# SingleBoard.net
KiCad netlist of a schematic drawn in EAGLE
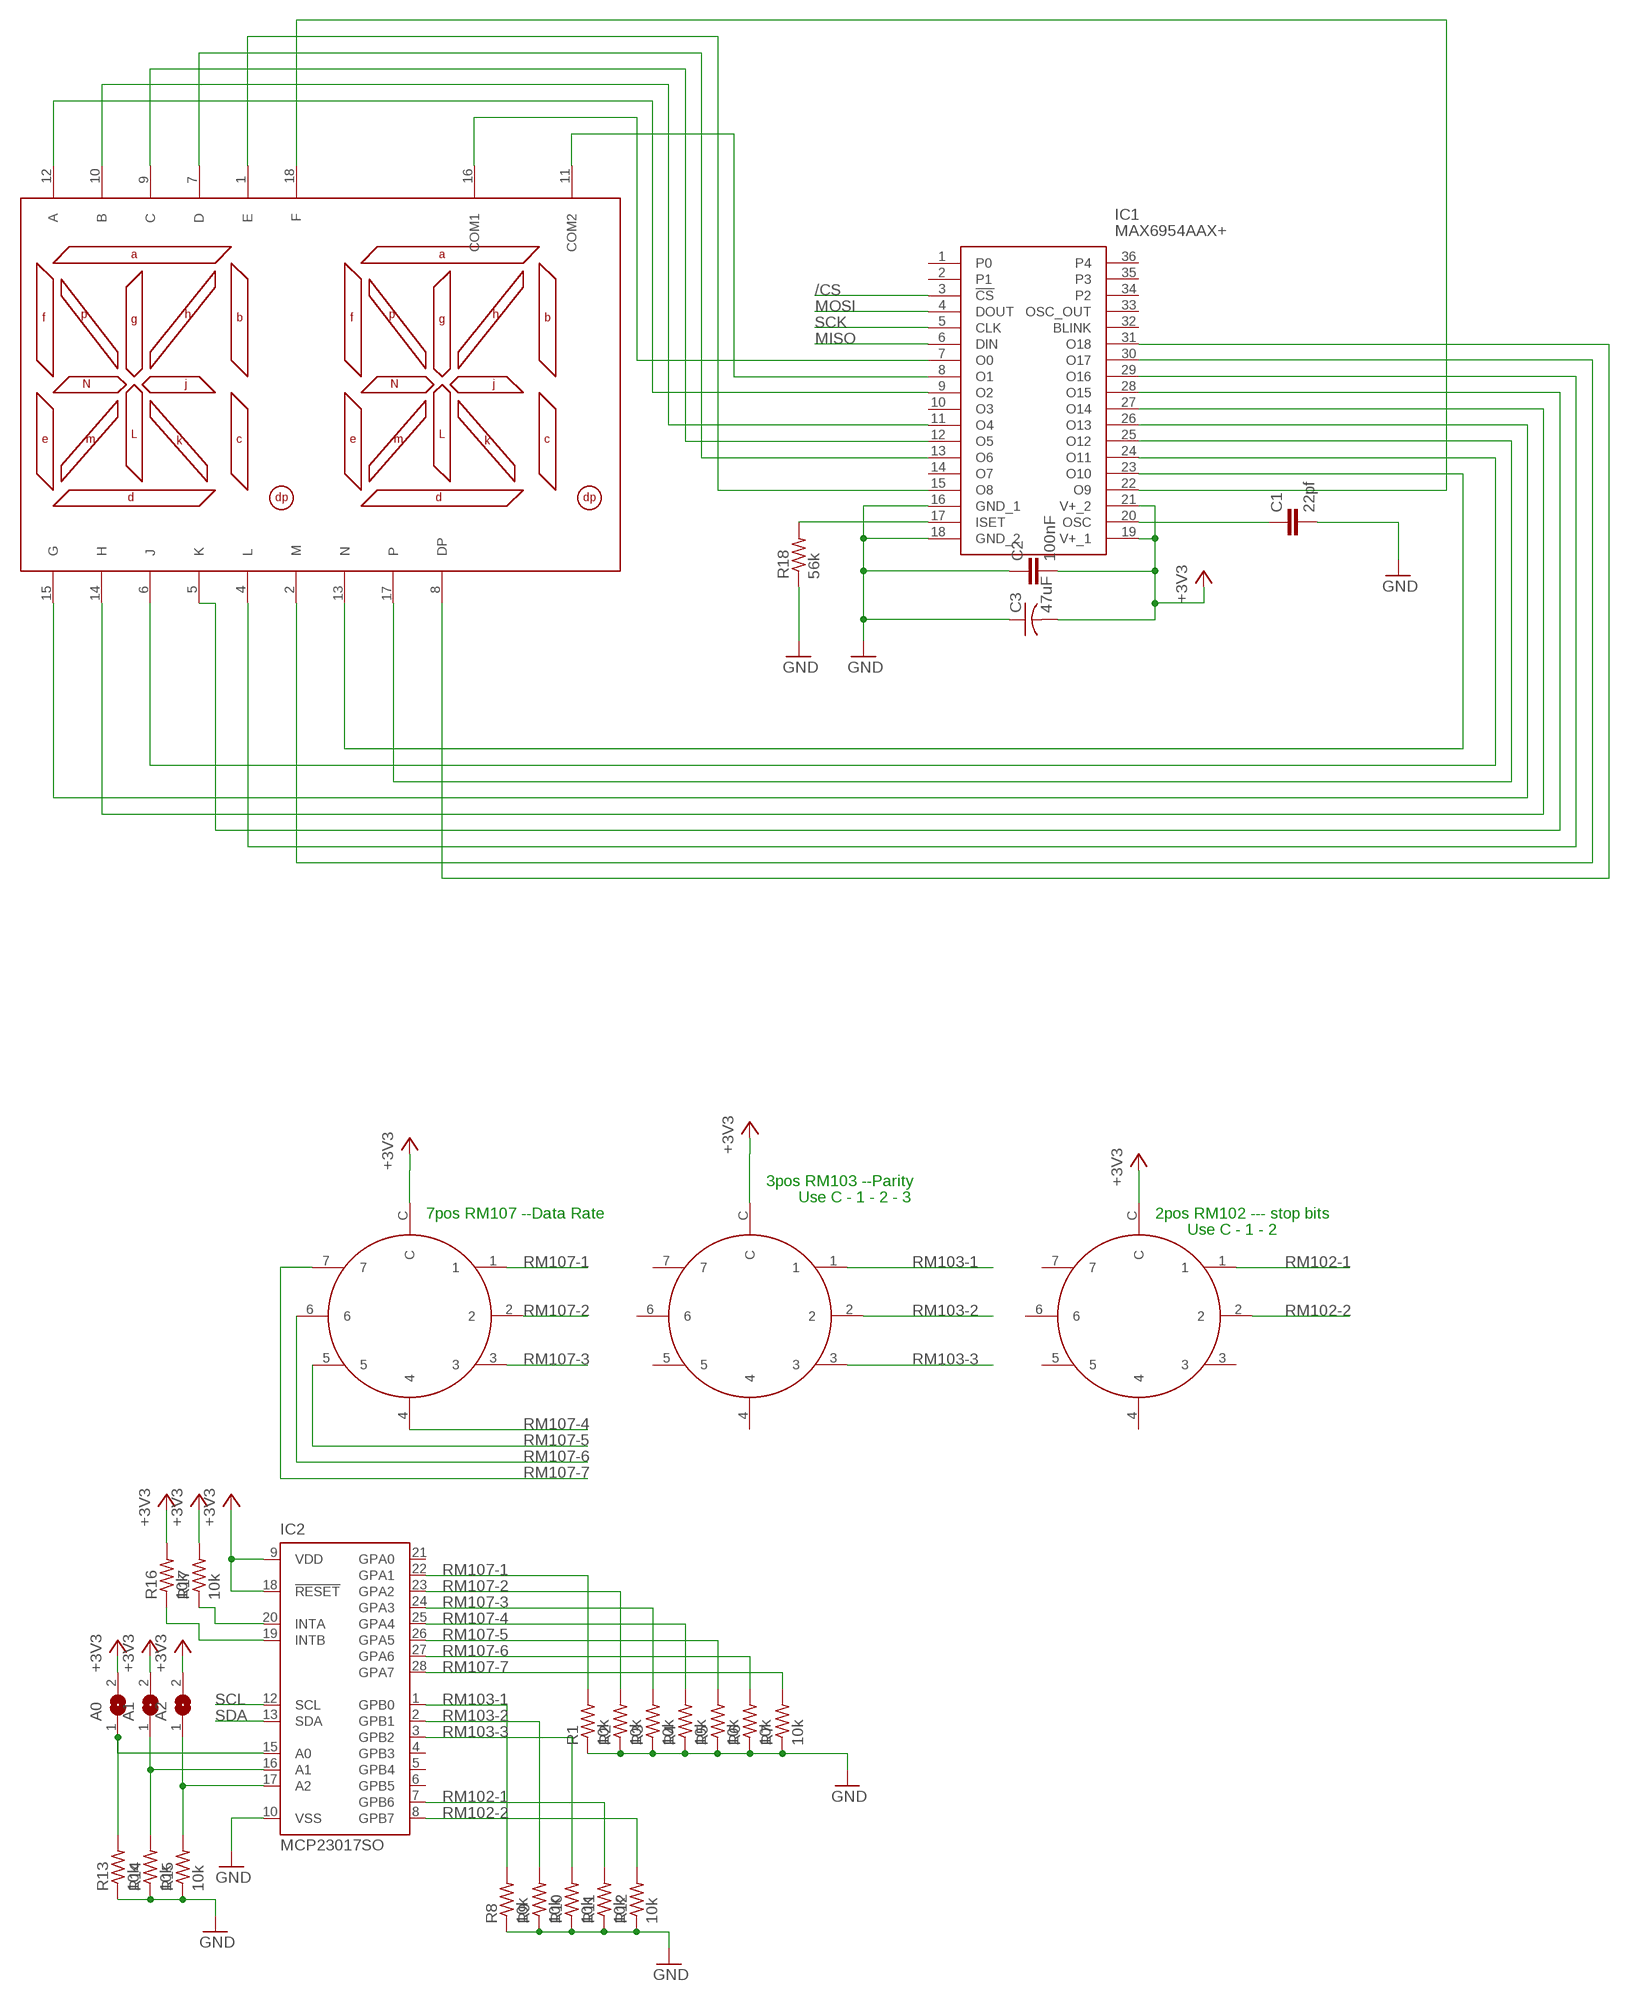
[diagram p0: schematic, sheet 1, part 1 of 2]
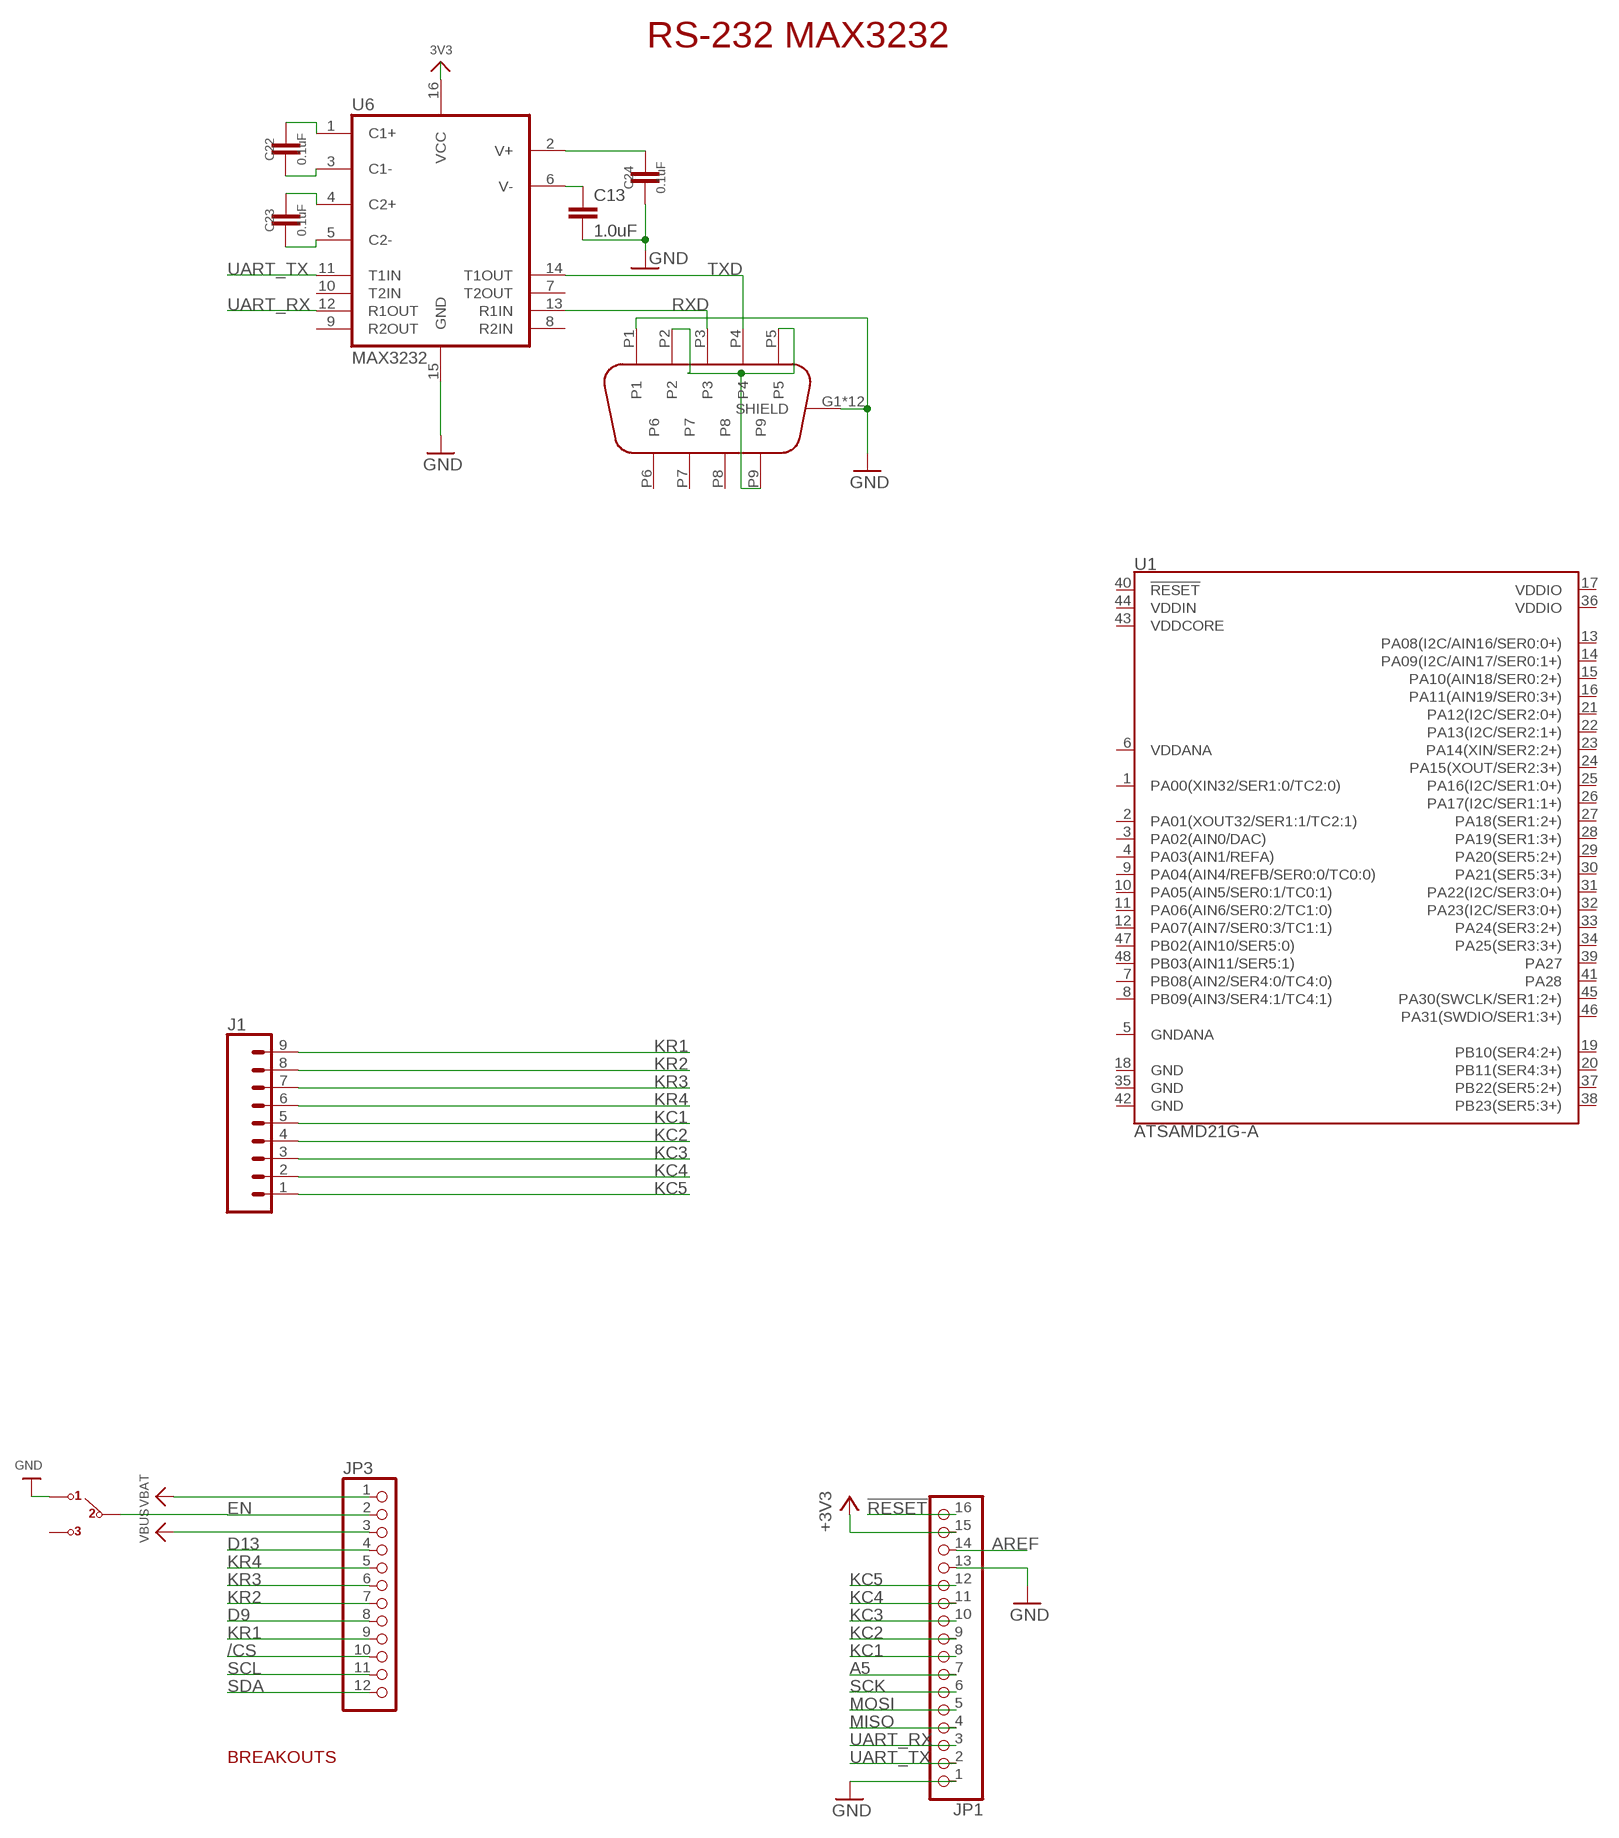
[diagram p1: schematic, sheet 1, part 2 of 2]

(export (version "E")
  (design (tool "Eeschema 10.0.6"))
  (components
    (comp (ref "A0") (value "SJ") (footprint "eagle-import:SJ") (libsource (lib "eagle-import") (part "SJ")))
    (comp (ref "A1") (value "SJ") (footprint "eagle-import:SJ") (libsource (lib "eagle-import") (part "SJ")))
    (comp (ref "A2") (value "SJ") (footprint "eagle-import:SJ") (libsource (lib "eagle-import") (part "SJ")))
    (comp (ref "C1")
      (value "22pf")
      (footprint "eagle-import:0805")
      (libsource (lib "eagle-import") (part "1.0UF-0805-25V-(+80/-20%)"))
    )
    (comp (ref "C2")
      (value "100nF")
      (footprint "eagle-import:0805")
      (libsource (lib "eagle-import") (part "1.0UF-0805-25V-(+80/-20%)"))
    )
    (comp (ref "C3")
      (value "47uF")
      (footprint "eagle-import:C1206")
      (libsource (lib "eagle-import") (part "C-USC1206"))
    )
    (comp (ref "C13")
      (value "1.0uF")
      (footprint "eagle-import:0805")
      (libsource (lib "eagle-import") (part "1.0UF-0805-25V-10%"))
    )
    (comp (ref "C22")
      (value "0.1uF")
      (footprint "eagle-import:0805")
      (libsource (lib "eagle-import") (part "1.0UF-0805-25V-10%"))
    )
    (comp (ref "C23")
      (value "0.1uF")
      (footprint "eagle-import:0805")
      (libsource (lib "eagle-import") (part "1.0UF-0805-25V-10%"))
    )
    (comp (ref "C24")
      (value "0.1uF")
      (footprint "eagle-import:0805")
      (libsource (lib "eagle-import") (part "1.0UF-0805-25V-10%"))
    )
    (comp (ref "DE9FEMALE")
      (value "EDGEMOUNTDE9")
      (footprint "eagle-import:DE09S065TLF")
      (libsource (lib "eagle-import") (part "EDGEMOUNTDE9"))
    )
    (comp (ref "IC1")
      (value "MAX6954AAX+")
      (footprint "eagle-import:SOP80P1030X264-36N")
      (fields (field (name "MOUSER_PART_NUMBER") "700-MAX6954AAX"))
      (libsource (lib "eagle-import") (part "MAX6954AAX+"))
    )
    (comp (ref "IC2")
      (value "MCP23017SO")
      (footprint "eagle-import:SO28W")
      (libsource (lib "eagle-import") (part "MCP23017SO"))
    )
    (comp (ref "J1")
      (value "CONN_09")
      (footprint "eagle-import:1X09")
      (libsource (lib "eagle-import") (part "CONN_09"))
    )
    (comp (ref "JP1")
      (value "HEADER-1X16ROUND")
      (footprint "eagle-import:1X16_ROUND")
      (libsource (lib "eagle-import") (part "HEADER-1X16ROUND"))
    )
    (comp (ref "JP3")
      (value "HEADER-1X12")
      (footprint "eagle-import:1X12_ROUND")
      (libsource (lib "eagle-import") (part "HEADER-1X12"))
    )
    (comp (ref "R1")
      (value "10k")
      (footprint "eagle-import:M0805")
      (libsource (lib "eagle-import") (part "R-US_M0805"))
    )
    (comp (ref "R2")
      (value "10k")
      (footprint "eagle-import:M0805")
      (libsource (lib "eagle-import") (part "R-US_M0805"))
    )
    (comp (ref "R3")
      (value "10k")
      (footprint "eagle-import:M0805")
      (libsource (lib "eagle-import") (part "R-US_M0805"))
    )
    (comp (ref "R4")
      (value "10k")
      (footprint "eagle-import:M0805")
      (libsource (lib "eagle-import") (part "R-US_M0805"))
    )
    (comp (ref "R5")
      (value "10k")
      (footprint "eagle-import:M0805")
      (libsource (lib "eagle-import") (part "R-US_M0805"))
    )
    (comp (ref "R6")
      (value "10k")
      (footprint "eagle-import:M0805")
      (libsource (lib "eagle-import") (part "R-US_M0805"))
    )
    (comp (ref "R7")
      (value "10k")
      (footprint "eagle-import:M0805")
      (libsource (lib "eagle-import") (part "R-US_M0805"))
    )
    (comp (ref "R8")
      (value "10k")
      (footprint "eagle-import:M0805")
      (libsource (lib "eagle-import") (part "R-US_M0805"))
    )
    (comp (ref "R9")
      (value "10k")
      (footprint "eagle-import:M0805")
      (libsource (lib "eagle-import") (part "R-US_M0805"))
    )
    (comp (ref "R10")
      (value "10k")
      (footprint "eagle-import:M0805")
      (libsource (lib "eagle-import") (part "R-US_M0805"))
    )
    (comp (ref "R11")
      (value "10k")
      (footprint "eagle-import:M0805")
      (libsource (lib "eagle-import") (part "R-US_M0805"))
    )
    (comp (ref "R12")
      (value "10k")
      (footprint "eagle-import:M0805")
      (libsource (lib "eagle-import") (part "R-US_M0805"))
    )
    (comp (ref "R13")
      (value "10k")
      (footprint "eagle-import:M0805")
      (libsource (lib "eagle-import") (part "R-US_M0805"))
    )
    (comp (ref "R14")
      (value "10k")
      (footprint "eagle-import:M0805")
      (libsource (lib "eagle-import") (part "R-US_M0805"))
    )
    (comp (ref "R15")
      (value "10k")
      (footprint "eagle-import:M0805")
      (libsource (lib "eagle-import") (part "R-US_M0805"))
    )
    (comp (ref "R16")
      (value "10k")
      (footprint "eagle-import:M0805")
      (libsource (lib "eagle-import") (part "R-US_M0805"))
    )
    (comp (ref "R17")
      (value "10k")
      (footprint "eagle-import:M0805")
      (libsource (lib "eagle-import") (part "R-US_M0805"))
    )
    (comp (ref "R18")
      (value "56k")
      (footprint "eagle-import:M0805")
      (libsource (lib "eagle-import") (part "R-US_M0805"))
    )
    (comp (ref "U$1")
      (value "BIG14SEG")
      (footprint "eagle-import:HDSP")
      (libsource (lib "eagle-import") (part "BIG14SEG"))
    )
    (comp (ref "U$2")
      (value "RM107772BCB")
      (footprint "eagle-import:RM107772BCB")
      (libsource (lib "eagle-import") (part "RM107772BCB"))
    )
    (comp (ref "U$3")
      (value "RM107772BCB")
      (footprint "eagle-import:RM107772BCB")
      (libsource (lib "eagle-import") (part "RM107772BCB"))
    )
    (comp (ref "U$5")
      (value "OS102011MA1QN1")
      (footprint "eagle-import:OS102011MA1QN1")
      (libsource (lib "eagle-import") (part "OS102011MA1QN1"))
    )
    (comp (ref "U$6")
      (value "RM107772BCB")
      (footprint "eagle-import:RM107772BCB")
      (libsource (lib "eagle-import") (part "RM107772BCB"))
    )
    (comp (ref "U1")
      (value "ATSAMD21G-A")
      (footprint "eagle-import:TQFP-48")
      (libsource (lib "eagle-import") (part "ATSAMD21G-A"))
    )
    (comp (ref "U6")
      (value "MAX3232")
      (footprint "eagle-import:SO16")
      (libsource (lib "eagle-import") (part "MAX2323SOIC16"))
    )
  )
  (nets
    (net (code "1") (name "+3V3") (class "Default")
      (node (ref "A0") (pin "2") (pinfunction "2_2") (pintype "passive"))
      (node (ref "A1") (pin "2") (pinfunction "2_2") (pintype "passive"))
      (node (ref "A2") (pin "2") (pinfunction "2_2") (pintype "passive"))
      (node (ref "C2") (pin "2") (pinfunction "2_2") (pintype "passive"))
      (node (ref "C3") (pin "2") (pinfunction "2_2") (pintype "passive"))
      (node (ref "IC1") (pin "19") (pinfunction "V+_1_19") (pintype "bidirectional"))
      (node (ref "IC1") (pin "21") (pinfunction "V+_2_21") (pintype "bidirectional"))
      (node (ref "IC2") (pin "18") (pinfunction "~{RESET}_18") (pintype "input"))
      (node (ref "IC2") (pin "9") (pinfunction "VDD_9") (pintype "power_in"))
      (node (ref "JP1") (pin "15") (pinfunction "15_15") (pintype "passive"))
      (node (ref "R16") (pin "2") (pinfunction "2_2") (pintype "passive"))
      (node (ref "R17") (pin "2") (pinfunction "2_2") (pintype "passive"))
      (node (ref "U$2") (pin "C") (pinfunction "C_C") (pintype "bidirectional"))
      (node (ref "U$3") (pin "C") (pinfunction "C_C") (pintype "bidirectional"))
      (node (ref "U$6") (pin "C") (pinfunction "C_C") (pintype "bidirectional"))
    )
    (net (code "2") (name "/A5") (class "Default")
      (node (ref "JP1") (pin "7") (pinfunction "7_7") (pintype "passive"))
    )
    (net (code "3") (name "/AREF") (class "Default")
      (node (ref "JP1") (pin "14") (pinfunction "14_14") (pintype "passive"))
    )
    (net (code "4") (name "/D9") (class "Default")
      (node (ref "JP3") (pin "8") (pinfunction "8_8") (pintype "passive"))
    )
    (net (code "5") (name "/D13") (class "Default")
      (node (ref "JP3") (pin "4") (pinfunction "4_4") (pintype "passive"))
    )
    (net (code "6") (name "/EN") (class "Default")
      (node (ref "JP3") (pin "2") (pinfunction "2_2") (pintype "passive"))
      (node (ref "U$5") (pin "P$2") (pinfunction "P$2_P$2") (pintype "bidirectional"))
    )
    (net (code "7") (name "/KC1") (class "Default")
      (node (ref "J1") (pin "5") (pinfunction "5_5") (pintype "passive"))
      (node (ref "JP1") (pin "8") (pinfunction "8_8") (pintype "passive"))
    )
    (net (code "8") (name "/KC2") (class "Default")
      (node (ref "J1") (pin "4") (pinfunction "4_4") (pintype "passive"))
      (node (ref "JP1") (pin "9") (pinfunction "9_9") (pintype "passive"))
    )
    (net (code "9") (name "/KC3") (class "Default")
      (node (ref "J1") (pin "3") (pinfunction "3_3") (pintype "passive"))
      (node (ref "JP1") (pin "10") (pinfunction "10_10") (pintype "passive"))
    )
    (net (code "10") (name "/KC4") (class "Default")
      (node (ref "J1") (pin "2") (pinfunction "2_2") (pintype "passive"))
      (node (ref "JP1") (pin "11") (pinfunction "11_11") (pintype "passive"))
    )
    (net (code "11") (name "/KC5") (class "Default")
      (node (ref "J1") (pin "1") (pinfunction "1_1") (pintype "passive"))
      (node (ref "JP1") (pin "12") (pinfunction "12_12") (pintype "passive"))
    )
    (net (code "12") (name "/KR1") (class "Default")
      (node (ref "J1") (pin "9") (pinfunction "9_9") (pintype "passive"))
      (node (ref "JP3") (pin "9") (pinfunction "9_9") (pintype "passive"))
    )
    (net (code "13") (name "/KR2") (class "Default")
      (node (ref "J1") (pin "8") (pinfunction "8_8") (pintype "passive"))
      (node (ref "JP3") (pin "7") (pinfunction "7_7") (pintype "passive"))
    )
    (net (code "14") (name "/KR3") (class "Default")
      (node (ref "J1") (pin "7") (pinfunction "7_7") (pintype "passive"))
      (node (ref "JP3") (pin "6") (pinfunction "6_6") (pintype "passive"))
    )
    (net (code "15") (name "/KR4") (class "Default")
      (node (ref "J1") (pin "6") (pinfunction "6_6") (pintype "passive"))
      (node (ref "JP3") (pin "5") (pinfunction "5_5") (pintype "passive"))
    )
    (net (code "16") (name "/MISO") (class "Default")
      (node (ref "IC1") (pin "6") (pinfunction "DIN_6") (pintype "input"))
      (node (ref "JP1") (pin "4") (pinfunction "4_4") (pintype "passive"))
    )
    (net (code "17") (name "/MOSI") (class "Default")
      (node (ref "IC1") (pin "4") (pinfunction "DOUT_4") (pintype "output"))
      (node (ref "JP1") (pin "5") (pinfunction "5_5") (pintype "passive"))
    )
    (net (code "18") (name "/RM102-1") (class "Default")
      (node (ref "IC2") (pin "7") (pinfunction "GPB6_7") (pintype "bidirectional"))
      (node (ref "R11") (pin "2") (pinfunction "2_2") (pintype "passive"))
      (node (ref "U$6") (pin "1") (pinfunction "1_1") (pintype "bidirectional"))
    )
    (net (code "19") (name "/RM102-2") (class "Default")
      (node (ref "IC2") (pin "8") (pinfunction "GPB7_8") (pintype "bidirectional"))
      (node (ref "R12") (pin "2") (pinfunction "2_2") (pintype "passive"))
      (node (ref "U$6") (pin "2") (pinfunction "2_2") (pintype "bidirectional"))
    )
    (net (code "20") (name "/RM103-1") (class "Default")
      (node (ref "IC2") (pin "1") (pinfunction "GPB0_1") (pintype "bidirectional"))
      (node (ref "R8") (pin "2") (pinfunction "2_2") (pintype "passive"))
      (node (ref "U$3") (pin "1") (pinfunction "1_1") (pintype "bidirectional"))
    )
    (net (code "21") (name "/RM103-2") (class "Default")
      (node (ref "IC2") (pin "2") (pinfunction "GPB1_2") (pintype "bidirectional"))
      (node (ref "R9") (pin "2") (pinfunction "2_2") (pintype "passive"))
      (node (ref "U$3") (pin "2") (pinfunction "2_2") (pintype "bidirectional"))
    )
    (net (code "22") (name "/RM103-3") (class "Default")
      (node (ref "IC2") (pin "3") (pinfunction "GPB2_3") (pintype "bidirectional"))
      (node (ref "R10") (pin "2") (pinfunction "2_2") (pintype "passive"))
      (node (ref "U$3") (pin "3") (pinfunction "3_3") (pintype "bidirectional"))
    )
    (net (code "23") (name "/RM107-1") (class "Default")
      (node (ref "IC2") (pin "22") (pinfunction "GPA1_22") (pintype "bidirectional"))
      (node (ref "R1") (pin "2") (pinfunction "2_2") (pintype "passive"))
      (node (ref "U$2") (pin "1") (pinfunction "1_1") (pintype "bidirectional"))
    )
    (net (code "24") (name "/RM107-2") (class "Default")
      (node (ref "IC2") (pin "23") (pinfunction "GPA2_23") (pintype "bidirectional"))
      (node (ref "R2") (pin "2") (pinfunction "2_2") (pintype "passive"))
      (node (ref "U$2") (pin "2") (pinfunction "2_2") (pintype "bidirectional"))
    )
    (net (code "25") (name "/RM107-3") (class "Default")
      (node (ref "IC2") (pin "24") (pinfunction "GPA3_24") (pintype "bidirectional"))
      (node (ref "R3") (pin "2") (pinfunction "2_2") (pintype "passive"))
      (node (ref "U$2") (pin "3") (pinfunction "3_3") (pintype "bidirectional"))
    )
    (net (code "26") (name "/RM107-4") (class "Default")
      (node (ref "IC2") (pin "25") (pinfunction "GPA4_25") (pintype "bidirectional"))
      (node (ref "R4") (pin "2") (pinfunction "2_2") (pintype "passive"))
      (node (ref "U$2") (pin "4") (pinfunction "4_4") (pintype "bidirectional"))
    )
    (net (code "27") (name "/RM107-5") (class "Default")
      (node (ref "IC2") (pin "26") (pinfunction "GPA5_26") (pintype "bidirectional"))
      (node (ref "R5") (pin "2") (pinfunction "2_2") (pintype "passive"))
      (node (ref "U$2") (pin "5") (pinfunction "5_5") (pintype "bidirectional"))
    )
    (net (code "28") (name "/RM107-6") (class "Default")
      (node (ref "IC2") (pin "27") (pinfunction "GPA6_27") (pintype "bidirectional"))
      (node (ref "R6") (pin "2") (pinfunction "2_2") (pintype "passive"))
      (node (ref "U$2") (pin "6") (pinfunction "6_6") (pintype "bidirectional"))
    )
    (net (code "29") (name "/RM107-7") (class "Default")
      (node (ref "IC2") (pin "28") (pinfunction "GPA7_28") (pintype "bidirectional"))
      (node (ref "R7") (pin "2") (pinfunction "2_2") (pintype "passive"))
      (node (ref "U$2") (pin "7") (pinfunction "7_7") (pintype "bidirectional"))
    )
    (net (code "30") (name "/RXD") (class "Default")
      (node (ref "DE9FEMALE") (pin "P3") (pinfunction "P3_P3") (pintype "bidirectional"))
      (node (ref "U6") (pin "13") (pinfunction "R1IN_13") (pintype "input"))
    )
    (net (code "31") (name "/SCK") (class "Default")
      (node (ref "IC1") (pin "5") (pinfunction "CLK_5") (pintype "input"))
      (node (ref "JP1") (pin "6") (pinfunction "6_6") (pintype "passive"))
    )
    (net (code "32") (name "/SCL") (class "Default")
      (node (ref "IC2") (pin "12") (pinfunction "SCL_12") (pintype "input"))
      (node (ref "JP3") (pin "11") (pinfunction "11_11") (pintype "passive"))
    )
    (net (code "33") (name "/SDA") (class "Default")
      (node (ref "IC2") (pin "13") (pinfunction "SDA_13") (pintype "bidirectional"))
      (node (ref "JP3") (pin "12") (pinfunction "12_12") (pintype "passive"))
    )
    (net (code "34") (name "/TXD") (class "Default")
      (node (ref "DE9FEMALE") (pin "P4") (pinfunction "P4_P4") (pintype "bidirectional"))
      (node (ref "U6") (pin "14") (pinfunction "T1OUT_14") (pintype "output"))
    )
    (net (code "35") (name "/UART_RX") (class "Default")
      (node (ref "JP1") (pin "3") (pinfunction "3_3") (pintype "passive"))
      (node (ref "U6") (pin "12") (pinfunction "R1OUT_12") (pintype "output"))
    )
    (net (code "36") (name "/UART_TX") (class "Default")
      (node (ref "JP1") (pin "2") (pinfunction "2_2") (pintype "passive"))
      (node (ref "U6") (pin "11") (pinfunction "T1IN_11") (pintype "input"))
    )
    (net (code "37") (name "/{slash}CS") (class "Default")
      (node (ref "IC1") (pin "3") (pinfunction "~{CS}_3") (pintype "input"))
      (node (ref "JP3") (pin "10") (pinfunction "10_10") (pintype "passive"))
    )
    (net (code "38") (name "/~{RESET}") (class "Default")
      (node (ref "JP1") (pin "16") (pinfunction "16_16") (pintype "passive"))
    )
    (net (code "39") (name "3V3") (class "Default")
      (node (ref "U6") (pin "16") (pinfunction "VCC_16") (pintype "bidirectional"))
    )
    (net (code "40") (name "GND") (class "Default")
      (node (ref "C1") (pin "2") (pinfunction "2_2") (pintype "passive"))
      (node (ref "C13") (pin "2") (pinfunction "2_2") (pintype "passive"))
      (node (ref "C2") (pin "1") (pinfunction "1_1") (pintype "passive"))
      (node (ref "C24") (pin "2") (pinfunction "2_2") (pintype "passive"))
      (node (ref "C3") (pin "1") (pinfunction "1_1") (pintype "passive"))
      (node (ref "DE9FEMALE") (pin "G1") (pinfunction "SHIELD_G1") (pintype "bidirectional"))
      (node (ref "DE9FEMALE") (pin "G10") (pinfunction "SHIELD_G10") (pintype "bidirectional"))
      (node (ref "DE9FEMALE") (pin "G11") (pinfunction "SHIELD_G11") (pintype "bidirectional"))
      (node (ref "DE9FEMALE") (pin "G12") (pinfunction "SHIELD_G12") (pintype "bidirectional"))
      (node (ref "DE9FEMALE") (pin "G2") (pinfunction "SHIELD_G2") (pintype "bidirectional"))
      (node (ref "DE9FEMALE") (pin "G3") (pinfunction "SHIELD_G3") (pintype "bidirectional"))
      (node (ref "DE9FEMALE") (pin "G4") (pinfunction "SHIELD_G4") (pintype "bidirectional"))
      (node (ref "DE9FEMALE") (pin "G5") (pinfunction "SHIELD_G5") (pintype "bidirectional"))
      (node (ref "DE9FEMALE") (pin "G6") (pinfunction "SHIELD_G6") (pintype "bidirectional"))
      (node (ref "DE9FEMALE") (pin "G7") (pinfunction "SHIELD_G7") (pintype "bidirectional"))
      (node (ref "DE9FEMALE") (pin "G8") (pinfunction "SHIELD_G8") (pintype "bidirectional"))
      (node (ref "DE9FEMALE") (pin "G9") (pinfunction "SHIELD_G9") (pintype "bidirectional"))
      (node (ref "DE9FEMALE") (pin "P1") (pinfunction "P1_P1") (pintype "bidirectional"))
      (node (ref "IC1") (pin "16") (pinfunction "GND_1_16") (pintype "power_in"))
      (node (ref "IC1") (pin "18") (pinfunction "GND_2_18") (pintype "power_in"))
      (node (ref "IC2") (pin "10") (pinfunction "VSS_10") (pintype "power_in"))
      (node (ref "JP1") (pin "1") (pinfunction "1_1") (pintype "passive"))
      (node (ref "JP1") (pin "13") (pinfunction "13_13") (pintype "passive"))
      (node (ref "R1") (pin "1") (pinfunction "1_1") (pintype "passive"))
      (node (ref "R10") (pin "1") (pinfunction "1_1") (pintype "passive"))
      (node (ref "R11") (pin "1") (pinfunction "1_1") (pintype "passive"))
      (node (ref "R12") (pin "1") (pinfunction "1_1") (pintype "passive"))
      (node (ref "R13") (pin "1") (pinfunction "1_1") (pintype "passive"))
      (node (ref "R14") (pin "1") (pinfunction "1_1") (pintype "passive"))
      (node (ref "R15") (pin "1") (pinfunction "1_1") (pintype "passive"))
      (node (ref "R18") (pin "1") (pinfunction "1_1") (pintype "passive"))
      (node (ref "R2") (pin "1") (pinfunction "1_1") (pintype "passive"))
      (node (ref "R3") (pin "1") (pinfunction "1_1") (pintype "passive"))
      (node (ref "R4") (pin "1") (pinfunction "1_1") (pintype "passive"))
      (node (ref "R5") (pin "1") (pinfunction "1_1") (pintype "passive"))
      (node (ref "R6") (pin "1") (pinfunction "1_1") (pintype "passive"))
      (node (ref "R7") (pin "1") (pinfunction "1_1") (pintype "passive"))
      (node (ref "R8") (pin "1") (pinfunction "1_1") (pintype "passive"))
      (node (ref "R9") (pin "1") (pinfunction "1_1") (pintype "passive"))
      (node (ref "U$5") (pin "P$1") (pinfunction "P$1_P$1") (pintype "bidirectional"))
      (node (ref "U6") (pin "15") (pinfunction "GND_15") (pintype "bidirectional"))
    )
    (net (code "41") (name "Net-(DE9FEMALE-PadP2)") (class "Default")
      (node (ref "DE9FEMALE") (pin "P2") (pinfunction "P2_P2") (pintype "bidirectional"))
      (node (ref "DE9FEMALE") (pin "P5") (pinfunction "P5_P5") (pintype "bidirectional"))
      (node (ref "DE9FEMALE") (pin "P9") (pinfunction "P9_P9") (pintype "bidirectional"))
    )
    (net (code "42") (name "Net-(IC1-ISET)") (class "Default")
      (node (ref "IC1") (pin "17") (pinfunction "ISET_17") (pintype "bidirectional"))
      (node (ref "R18") (pin "2") (pinfunction "2_2") (pintype "passive"))
    )
    (net (code "43") (name "Net-(IC1-O0)") (class "Default")
      (node (ref "IC1") (pin "7") (pinfunction "O0_7") (pintype "output"))
      (node (ref "U$1") (pin "16") (pinfunction "COM1_16") (pintype "bidirectional"))
    )
    (net (code "44") (name "Net-(IC1-O1)") (class "Default")
      (node (ref "IC1") (pin "8") (pinfunction "O1_8") (pintype "output"))
      (node (ref "U$1") (pin "11") (pinfunction "COM2_11") (pintype "bidirectional"))
    )
    (net (code "45") (name "Net-(IC1-O2)") (class "Default")
      (node (ref "IC1") (pin "9") (pinfunction "O2_9") (pintype "output"))
      (node (ref "U$1") (pin "12") (pinfunction "A_12") (pintype "bidirectional"))
    )
    (net (code "46") (name "Net-(IC1-O4)") (class "Default")
      (node (ref "IC1") (pin "11") (pinfunction "O4_11") (pintype "output"))
      (node (ref "U$1") (pin "10") (pinfunction "B_10") (pintype "bidirectional"))
    )
    (net (code "47") (name "Net-(IC1-O5)") (class "Default")
      (node (ref "IC1") (pin "12") (pinfunction "O5_12") (pintype "output"))
      (node (ref "U$1") (pin "9") (pinfunction "C_9") (pintype "bidirectional"))
    )
    (net (code "48") (name "Net-(IC1-O6)") (class "Default")
      (node (ref "IC1") (pin "13") (pinfunction "O6_13") (pintype "output"))
      (node (ref "U$1") (pin "7") (pinfunction "D_7") (pintype "bidirectional"))
    )
    (net (code "49") (name "Net-(IC1-O8)") (class "Default")
      (node (ref "IC1") (pin "15") (pinfunction "O8_15") (pintype "output"))
      (node (ref "U$1") (pin "1") (pinfunction "E_1") (pintype "bidirectional"))
    )
    (net (code "50") (name "Net-(IC1-O9)") (class "Default")
      (node (ref "IC1") (pin "22") (pinfunction "O9_22") (pintype "bidirectional"))
      (node (ref "U$1") (pin "18") (pinfunction "F_18") (pintype "bidirectional"))
    )
    (net (code "51") (name "Net-(IC1-O10)") (class "Default")
      (node (ref "IC1") (pin "23") (pinfunction "O10_23") (pintype "bidirectional"))
      (node (ref "U$1") (pin "13") (pinfunction "N_13") (pintype "bidirectional"))
    )
    (net (code "52") (name "Net-(IC1-O11)") (class "Default")
      (node (ref "IC1") (pin "24") (pinfunction "O11_24") (pintype "bidirectional"))
      (node (ref "U$1") (pin "6") (pinfunction "J_6") (pintype "bidirectional"))
    )
    (net (code "53") (name "Net-(IC1-O12)") (class "Default")
      (node (ref "IC1") (pin "25") (pinfunction "O12_25") (pintype "bidirectional"))
      (node (ref "U$1") (pin "17") (pinfunction "P_17") (pintype "bidirectional"))
    )
    (net (code "54") (name "Net-(IC1-O13)") (class "Default")
      (node (ref "IC1") (pin "26") (pinfunction "O13_26") (pintype "bidirectional"))
      (node (ref "U$1") (pin "15") (pinfunction "G_15") (pintype "bidirectional"))
    )
    (net (code "55") (name "Net-(IC1-O14)") (class "Default")
      (node (ref "IC1") (pin "27") (pinfunction "O14_27") (pintype "bidirectional"))
      (node (ref "U$1") (pin "14") (pinfunction "H_14") (pintype "bidirectional"))
    )
    (net (code "56") (name "Net-(IC1-O15)") (class "Default")
      (node (ref "IC1") (pin "28") (pinfunction "O15_28") (pintype "bidirectional"))
      (node (ref "U$1") (pin "5") (pinfunction "K_5") (pintype "bidirectional"))
    )
    (net (code "57") (name "Net-(IC1-O16)") (class "Default")
      (node (ref "IC1") (pin "29") (pinfunction "O16_29") (pintype "bidirectional"))
      (node (ref "U$1") (pin "4") (pinfunction "L_4") (pintype "bidirectional"))
    )
    (net (code "58") (name "Net-(IC1-O17)") (class "Default")
      (node (ref "IC1") (pin "30") (pinfunction "O17_30") (pintype "bidirectional"))
      (node (ref "U$1") (pin "2") (pinfunction "M_2") (pintype "bidirectional"))
    )
    (net (code "59") (name "Net-(IC1-O18)") (class "Default")
      (node (ref "IC1") (pin "31") (pinfunction "O18_31") (pintype "bidirectional"))
      (node (ref "U$1") (pin "8") (pinfunction "DP_8") (pintype "bidirectional"))
    )
    (net (code "60") (name "Net-(IC1-OSC)") (class "Default")
      (node (ref "C1") (pin "1") (pinfunction "1_1") (pintype "passive"))
      (node (ref "IC1") (pin "20") (pinfunction "OSC_20") (pintype "bidirectional"))
    )
    (net (code "61") (name "Net-(IC2-A0)") (class "Default")
      (node (ref "A0") (pin "1") (pinfunction "1_1") (pintype "passive"))
      (node (ref "IC2") (pin "15") (pinfunction "A0_15") (pintype "input"))
      (node (ref "R13") (pin "2") (pinfunction "2_2") (pintype "passive"))
    )
    (net (code "62") (name "Net-(IC2-A1)") (class "Default")
      (node (ref "A1") (pin "1") (pinfunction "1_1") (pintype "passive"))
      (node (ref "IC2") (pin "16") (pinfunction "A1_16") (pintype "input"))
      (node (ref "R14") (pin "2") (pinfunction "2_2") (pintype "passive"))
    )
    (net (code "63") (name "Net-(IC2-A2)") (class "Default")
      (node (ref "A2") (pin "1") (pinfunction "1_1") (pintype "passive"))
      (node (ref "IC2") (pin "17") (pinfunction "A2_17") (pintype "input"))
      (node (ref "R15") (pin "2") (pinfunction "2_2") (pintype "passive"))
    )
    (net (code "64") (name "Net-(IC2-INTA)") (class "Default")
      (node (ref "IC2") (pin "20") (pinfunction "INTA_20") (pintype "output"))
      (node (ref "R17") (pin "1") (pinfunction "1_1") (pintype "passive"))
    )
    (net (code "65") (name "Net-(IC2-INTB)") (class "Default")
      (node (ref "IC2") (pin "19") (pinfunction "INTB_19") (pintype "output"))
      (node (ref "R16") (pin "1") (pinfunction "1_1") (pintype "passive"))
    )
    (net (code "66") (name "Net-(U6-C1+)") (class "Default")
      (node (ref "C22") (pin "1") (pinfunction "1_1") (pintype "passive"))
      (node (ref "U6") (pin "1") (pinfunction "C1+_1") (pintype "bidirectional"))
    )
    (net (code "67") (name "Net-(U6-C1-)") (class "Default")
      (node (ref "C22") (pin "2") (pinfunction "2_2") (pintype "passive"))
      (node (ref "U6") (pin "3") (pinfunction "C1-_3") (pintype "bidirectional"))
    )
    (net (code "68") (name "Net-(U6-C2+)") (class "Default")
      (node (ref "C23") (pin "1") (pinfunction "1_1") (pintype "passive"))
      (node (ref "U6") (pin "4") (pinfunction "C2+_4") (pintype "bidirectional"))
    )
    (net (code "69") (name "Net-(U6-C2-)") (class "Default")
      (node (ref "C23") (pin "2") (pinfunction "2_2") (pintype "passive"))
      (node (ref "U6") (pin "5") (pinfunction "C2-_5") (pintype "bidirectional"))
    )
    (net (code "70") (name "Net-(U6-V+)") (class "Default")
      (node (ref "C24") (pin "1") (pinfunction "1_1") (pintype "passive"))
      (node (ref "U6") (pin "2") (pinfunction "V+_2") (pintype "bidirectional"))
    )
    (net (code "71") (name "Net-(U6-V-)") (class "Default")
      (node (ref "C13") (pin "1") (pinfunction "1_1") (pintype "passive"))
      (node (ref "U6") (pin "6") (pinfunction "V-_6") (pintype "bidirectional"))
    )
    (net (code "72") (name "VBAT") (class "Default")
      (node (ref "JP3") (pin "1") (pinfunction "1_1") (pintype "passive"))
    )
    (net (code "73") (name "VBUS") (class "Default")
      (node (ref "JP3") (pin "3") (pinfunction "3_3") (pintype "passive"))
    )
    (net (code "74") (name "unconnected-(DE9FEMALE-PadP6)") (class "Default")
      (node (ref "DE9FEMALE") (pin "P6") (pinfunction "P6_P6") (pintype "bidirectional"))
    )
    (net (code "75") (name "unconnected-(DE9FEMALE-PadP7)") (class "Default")
      (node (ref "DE9FEMALE") (pin "P7") (pinfunction "P7_P7") (pintype "bidirectional"))
    )
    (net (code "76") (name "unconnected-(DE9FEMALE-PadP8)") (class "Default")
      (node (ref "DE9FEMALE") (pin "P8") (pinfunction "P8_P8") (pintype "bidirectional"))
    )
    (net (code "77") (name "unconnected-(IC1-BLINK-Pad32)") (class "Default")
      (node (ref "IC1") (pin "32") (pinfunction "BLINK_32") (pintype "input"))
    )
    (net (code "78") (name "unconnected-(IC1-O3-Pad10)") (class "Default")
      (node (ref "IC1") (pin "10") (pinfunction "O3_10") (pintype "output"))
    )
    (net (code "79") (name "unconnected-(IC1-O7-Pad14)") (class "Default")
      (node (ref "IC1") (pin "14") (pinfunction "O7_14") (pintype "output"))
    )
    (net (code "80") (name "unconnected-(IC1-OSC_OUT-Pad33)") (class "Default")
      (node (ref "IC1") (pin "33") (pinfunction "OSC_OUT_33") (pintype "output"))
    )
    (net (code "81") (name "unconnected-(IC1-P0-Pad1)") (class "Default")
      (node (ref "IC1") (pin "1") (pinfunction "P0_1") (pintype "bidirectional"))
    )
    (net (code "82") (name "unconnected-(IC1-P1-Pad2)") (class "Default")
      (node (ref "IC1") (pin "2") (pinfunction "P1_2") (pintype "bidirectional"))
    )
    (net (code "83") (name "unconnected-(IC1-P2-Pad34)") (class "Default")
      (node (ref "IC1") (pin "34") (pinfunction "P2_34") (pintype "bidirectional"))
    )
    (net (code "84") (name "unconnected-(IC1-P3-Pad35)") (class "Default")
      (node (ref "IC1") (pin "35") (pinfunction "P3_35") (pintype "bidirectional"))
    )
    (net (code "85") (name "unconnected-(IC1-P4-Pad36)") (class "Default")
      (node (ref "IC1") (pin "36") (pinfunction "P4_36") (pintype "bidirectional"))
    )
    (net (code "86") (name "unconnected-(IC2-GPA0-Pad21)") (class "Default")
      (node (ref "IC2") (pin "21") (pinfunction "GPA0_21") (pintype "bidirectional"))
    )
    (net (code "87") (name "unconnected-(IC2-GPB3-Pad4)") (class "Default")
      (node (ref "IC2") (pin "4") (pinfunction "GPB3_4") (pintype "bidirectional"))
    )
    (net (code "88") (name "unconnected-(IC2-GPB4-Pad5)") (class "Default")
      (node (ref "IC2") (pin "5") (pinfunction "GPB4_5") (pintype "bidirectional"))
    )
    (net (code "89") (name "unconnected-(IC2-GPB5-Pad6)") (class "Default")
      (node (ref "IC2") (pin "6") (pinfunction "GPB5_6") (pintype "bidirectional"))
    )
    (net (code "90") (name "unconnected-(U$3-Pad4)") (class "Default")
      (node (ref "U$3") (pin "4") (pinfunction "4_4") (pintype "bidirectional"))
    )
    (net (code "91") (name "unconnected-(U$3-Pad5)") (class "Default")
      (node (ref "U$3") (pin "5") (pinfunction "5_5") (pintype "bidirectional"))
    )
    (net (code "92") (name "unconnected-(U$3-Pad6)") (class "Default")
      (node (ref "U$3") (pin "6") (pinfunction "6_6") (pintype "bidirectional"))
    )
    (net (code "93") (name "unconnected-(U$3-Pad7)") (class "Default")
      (node (ref "U$3") (pin "7") (pinfunction "7_7") (pintype "bidirectional"))
    )
    (net (code "94") (name "unconnected-(U$5-CASE-PadCASE1)") (class "Default")
      (node (ref "U$5") (pin "CASE1") (pinfunction "CASE_CASE1") (pintype "no_connect"))
    )
    (net (code "95") (name "unconnected-(U$5-CASE-PadCASE2)") (class "Default")
      (node (ref "U$5") (pin "CASE2") (pinfunction "CASE_CASE2") (pintype "no_connect"))
    )
    (net (code "96") (name "unconnected-(U$5-PadP$3)") (class "Default")
      (node (ref "U$5") (pin "P$3") (pinfunction "P$3_P$3") (pintype "bidirectional"))
    )
    (net (code "97") (name "unconnected-(U$6-Pad3)") (class "Default")
      (node (ref "U$6") (pin "3") (pinfunction "3_3") (pintype "bidirectional"))
    )
    (net (code "98") (name "unconnected-(U$6-Pad4)") (class "Default")
      (node (ref "U$6") (pin "4") (pinfunction "4_4") (pintype "bidirectional"))
    )
    (net (code "99") (name "unconnected-(U$6-Pad5)") (class "Default")
      (node (ref "U$6") (pin "5") (pinfunction "5_5") (pintype "bidirectional"))
    )
    (net (code "100") (name "unconnected-(U$6-Pad6)") (class "Default")
      (node (ref "U$6") (pin "6") (pinfunction "6_6") (pintype "bidirectional"))
    )
    (net (code "101") (name "unconnected-(U$6-Pad7)") (class "Default")
      (node (ref "U$6") (pin "7") (pinfunction "7_7") (pintype "bidirectional"))
    )
    (net (code "102") (name "unconnected-(U1-GND-Pad18)") (class "Default")
      (node (ref "U1") (pin "18") (pinfunction "GND_18") (pintype "bidirectional"))
    )
    (net (code "103") (name "unconnected-(U1-GND-Pad35)") (class "Default")
      (node (ref "U1") (pin "35") (pinfunction "GND_35") (pintype "bidirectional"))
    )
    (net (code "104") (name "unconnected-(U1-GND-Pad42)") (class "Default")
      (node (ref "U1") (pin "42") (pinfunction "GND_42") (pintype "bidirectional"))
    )
    (net (code "105") (name "unconnected-(U1-GNDANA-Pad5)") (class "Default")
      (node (ref "U1") (pin "5") (pinfunction "GNDANA_5") (pintype "bidirectional"))
    )
    (net (code "106") (name "unconnected-(U1-PA00(XIN32{slash}SER1:0{slash}TC2:0)-Pad1)") (class "Default")
      (node (ref "U1") (pin "1") (pinfunction "PA00(XIN32/SER1:0/TC2:0)_1") (pintype "bidirectional"))
    )
    (net (code "107") (name "unconnected-(U1-PA01(XOUT32{slash}SER1:1{slash}TC2:1)-Pad2)") (class "Default")
      (node (ref "U1") (pin "2") (pinfunction "PA01(XOUT32/SER1:1/TC2:1)_2") (pintype "bidirectional"))
    )
    (net (code "108") (name "unconnected-(U1-PA02(AIN0{slash}DAC)-Pad3)") (class "Default")
      (node (ref "U1") (pin "3") (pinfunction "PA02(AIN0/DAC)_3") (pintype "bidirectional"))
    )
    (net (code "109") (name "unconnected-(U1-PA03(AIN1{slash}REFA)-Pad4)") (class "Default")
      (node (ref "U1") (pin "4") (pinfunction "PA03(AIN1/REFA)_4") (pintype "bidirectional"))
    )
    (net (code "110") (name "unconnected-(U1-PA04(AIN4{slash}REFB{slash}SER0:0{slash}TC0:0)-Pad9)") (class "Default")
      (node (ref "U1") (pin "9") (pinfunction "PA04(AIN4/REFB/SER0:0/TC0:0)_9") (pintype "bidirectional"))
    )
    (net (code "111") (name "unconnected-(U1-PA05(AIN5{slash}SER0:1{slash}TC0:1)-Pad10)") (class "Default")
      (node (ref "U1") (pin "10") (pinfunction "PA05(AIN5/SER0:1/TC0:1)_10") (pintype "bidirectional"))
    )
    (net (code "112") (name "unconnected-(U1-PA06(AIN6{slash}SER0:2{slash}TC1:0)-Pad11)") (class "Default")
      (node (ref "U1") (pin "11") (pinfunction "PA06(AIN6/SER0:2/TC1:0)_11") (pintype "bidirectional"))
    )
    (net (code "113") (name "unconnected-(U1-PA07(AIN7{slash}SER0:3{slash}TC1:1)-Pad12)") (class "Default")
      (node (ref "U1") (pin "12") (pinfunction "PA07(AIN7/SER0:3/TC1:1)_12") (pintype "bidirectional"))
    )
    (net (code "114") (name "unconnected-(U1-PA08(I2C{slash}AIN16{slash}SER0:0+)-Pad13)") (class "Default")
      (node (ref "U1") (pin "13") (pinfunction "PA08(I2C/AIN16/SER0:0+)_13") (pintype "bidirectional"))
    )
    (net (code "115") (name "unconnected-(U1-PA09(I2C{slash}AIN17{slash}SER0:1+)-Pad14)") (class "Default")
      (node (ref "U1") (pin "14") (pinfunction "PA09(I2C/AIN17/SER0:1+)_14") (pintype "bidirectional"))
    )
    (net (code "116") (name "unconnected-(U1-PA10(AIN18{slash}SER0:2+)-Pad15)") (class "Default")
      (node (ref "U1") (pin "15") (pinfunction "PA10(AIN18/SER0:2+)_15") (pintype "bidirectional"))
    )
    (net (code "117") (name "unconnected-(U1-PA11(AIN19{slash}SER0:3+)-Pad16)") (class "Default")
      (node (ref "U1") (pin "16") (pinfunction "PA11(AIN19/SER0:3+)_16") (pintype "bidirectional"))
    )
    (net (code "118") (name "unconnected-(U1-PA12(I2C{slash}SER2:0+)-Pad21)") (class "Default")
      (node (ref "U1") (pin "21") (pinfunction "PA12(I2C/SER2:0+)_21") (pintype "bidirectional"))
    )
    (net (code "119") (name "unconnected-(U1-PA13(I2C{slash}SER2:1+)-Pad22)") (class "Default")
      (node (ref "U1") (pin "22") (pinfunction "PA13(I2C/SER2:1+)_22") (pintype "bidirectional"))
    )
    (net (code "120") (name "unconnected-(U1-PA14(XIN{slash}SER2:2+)-Pad23)") (class "Default")
      (node (ref "U1") (pin "23") (pinfunction "PA14(XIN/SER2:2+)_23") (pintype "bidirectional"))
    )
    (net (code "121") (name "unconnected-(U1-PA15(XOUT{slash}SER2:3+)-Pad24)") (class "Default")
      (node (ref "U1") (pin "24") (pinfunction "PA15(XOUT/SER2:3+)_24") (pintype "bidirectional"))
    )
    (net (code "122") (name "unconnected-(U1-PA16(I2C{slash}SER1:0+)-Pad25)") (class "Default")
      (node (ref "U1") (pin "25") (pinfunction "PA16(I2C/SER1:0+)_25") (pintype "bidirectional"))
    )
    (net (code "123") (name "unconnected-(U1-PA17(I2C{slash}SER1:1+)-Pad26)") (class "Default")
      (node (ref "U1") (pin "26") (pinfunction "PA17(I2C/SER1:1+)_26") (pintype "bidirectional"))
    )
    (net (code "124") (name "unconnected-(U1-PA18(SER1:2+)-Pad27)") (class "Default")
      (node (ref "U1") (pin "27") (pinfunction "PA18(SER1:2+)_27") (pintype "bidirectional"))
    )
    (net (code "125") (name "unconnected-(U1-PA19(SER1:3+)-Pad28)") (class "Default")
      (node (ref "U1") (pin "28") (pinfunction "PA19(SER1:3+)_28") (pintype "bidirectional"))
    )
    (net (code "126") (name "unconnected-(U1-PA20(SER5:2+)-Pad29)") (class "Default")
      (node (ref "U1") (pin "29") (pinfunction "PA20(SER5:2+)_29") (pintype "bidirectional"))
    )
    (net (code "127") (name "unconnected-(U1-PA21(SER5:3+)-Pad30)") (class "Default")
      (node (ref "U1") (pin "30") (pinfunction "PA21(SER5:3+)_30") (pintype "bidirectional"))
    )
    (net (code "128") (name "unconnected-(U1-PA22(I2C{slash}SER3:0+)-Pad31)") (class "Default")
      (node (ref "U1") (pin "31") (pinfunction "PA22(I2C/SER3:0+)_31") (pintype "bidirectional"))
    )
    (net (code "129") (name "unconnected-(U1-PA23(I2C{slash}SER3:0+)-Pad32)") (class "Default")
      (node (ref "U1") (pin "32") (pinfunction "PA23(I2C/SER3:0+)_32") (pintype "bidirectional"))
    )
    (net (code "130") (name "unconnected-(U1-PA24(SER3:2+)-Pad33)") (class "Default")
      (node (ref "U1") (pin "33") (pinfunction "PA24(SER3:2+)_33") (pintype "bidirectional"))
    )
    (net (code "131") (name "unconnected-(U1-PA25(SER3:3+)-Pad34)") (class "Default")
      (node (ref "U1") (pin "34") (pinfunction "PA25(SER3:3+)_34") (pintype "bidirectional"))
    )
    (net (code "132") (name "unconnected-(U1-PA27-Pad39)") (class "Default")
      (node (ref "U1") (pin "39") (pinfunction "PA27_39") (pintype "bidirectional"))
    )
    (net (code "133") (name "unconnected-(U1-PA28-Pad41)") (class "Default")
      (node (ref "U1") (pin "41") (pinfunction "PA28_41") (pintype "bidirectional"))
    )
    (net (code "134") (name "unconnected-(U1-PA30(SWCLK{slash}SER1:2+)-Pad45)") (class "Default")
      (node (ref "U1") (pin "45") (pinfunction "PA30(SWCLK/SER1:2+)_45") (pintype "bidirectional"))
    )
    (net (code "135") (name "unconnected-(U1-PA31(SWDIO{slash}SER1:3+)-Pad46)") (class "Default")
      (node (ref "U1") (pin "46") (pinfunction "PA31(SWDIO/SER1:3+)_46") (pintype "bidirectional"))
    )
    (net (code "136") (name "unconnected-(U1-PB02(AIN10{slash}SER5:0)-Pad47)") (class "Default")
      (node (ref "U1") (pin "47") (pinfunction "PB02(AIN10/SER5:0)_47") (pintype "bidirectional"))
    )
    (net (code "137") (name "unconnected-(U1-PB03(AIN11{slash}SER5:1)-Pad48)") (class "Default")
      (node (ref "U1") (pin "48") (pinfunction "PB03(AIN11/SER5:1)_48") (pintype "bidirectional"))
    )
    (net (code "138") (name "unconnected-(U1-PB08(AIN2{slash}SER4:0{slash}TC4:0)-Pad7)") (class "Default")
      (node (ref "U1") (pin "7") (pinfunction "PB08(AIN2/SER4:0/TC4:0)_7") (pintype "bidirectional"))
    )
    (net (code "139") (name "unconnected-(U1-PB09(AIN3{slash}SER4:1{slash}TC4:1)-Pad8)") (class "Default")
      (node (ref "U1") (pin "8") (pinfunction "PB09(AIN3/SER4:1/TC4:1)_8") (pintype "bidirectional"))
    )
    (net (code "140") (name "unconnected-(U1-PB10(SER4:2+)-Pad19)") (class "Default")
      (node (ref "U1") (pin "19") (pinfunction "PB10(SER4:2+)_19") (pintype "bidirectional"))
    )
    (net (code "141") (name "unconnected-(U1-PB11(SER4:3+)-Pad20)") (class "Default")
      (node (ref "U1") (pin "20") (pinfunction "PB11(SER4:3+)_20") (pintype "bidirectional"))
    )
    (net (code "142") (name "unconnected-(U1-PB22(SER5:2+)-Pad37)") (class "Default")
      (node (ref "U1") (pin "37") (pinfunction "PB22(SER5:2+)_37") (pintype "bidirectional"))
    )
    (net (code "143") (name "unconnected-(U1-PB23(SER5:3+)-Pad38)") (class "Default")
      (node (ref "U1") (pin "38") (pinfunction "PB23(SER5:3+)_38") (pintype "bidirectional"))
    )
    (net (code "144") (name "unconnected-(U1-VDDANA-Pad6)") (class "Default")
      (node (ref "U1") (pin "6") (pinfunction "VDDANA_6") (pintype "bidirectional"))
    )
    (net (code "145") (name "unconnected-(U1-VDDCORE-Pad43)") (class "Default")
      (node (ref "U1") (pin "43") (pinfunction "VDDCORE_43") (pintype "bidirectional"))
    )
    (net (code "146") (name "unconnected-(U1-VDDIN-Pad44)") (class "Default")
      (node (ref "U1") (pin "44") (pinfunction "VDDIN_44") (pintype "bidirectional"))
    )
    (net (code "147") (name "unconnected-(U1-VDDIO-Pad17)") (class "Default")
      (node (ref "U1") (pin "17") (pinfunction "VDDIO_17") (pintype "bidirectional"))
    )
    (net (code "148") (name "unconnected-(U1-VDDIO-Pad36)") (class "Default")
      (node (ref "U1") (pin "36") (pinfunction "VDDIO_36") (pintype "bidirectional"))
    )
    (net (code "149") (name "unconnected-(U1-~{RESET}-Pad40)") (class "Default")
      (node (ref "U1") (pin "40") (pinfunction "~{RESET}_40") (pintype "bidirectional"))
    )
    (net (code "150") (name "unconnected-(U6-R2IN-Pad8)") (class "Default")
      (node (ref "U6") (pin "8") (pinfunction "R2IN_8") (pintype "input"))
    )
    (net (code "151") (name "unconnected-(U6-R2OUT-Pad9)") (class "Default")
      (node (ref "U6") (pin "9") (pinfunction "R2OUT_9") (pintype "output"))
    )
    (net (code "152") (name "unconnected-(U6-T2IN-Pad10)") (class "Default")
      (node (ref "U6") (pin "10") (pinfunction "T2IN_10") (pintype "input"))
    )
    (net (code "153") (name "unconnected-(U6-T2OUT-Pad7)") (class "Default")
      (node (ref "U6") (pin "7") (pinfunction "T2OUT_7") (pintype "output"))
    )
  )
)
